# stmsheet.net
KiCad netlist of a schematic drawn in Altium Designer
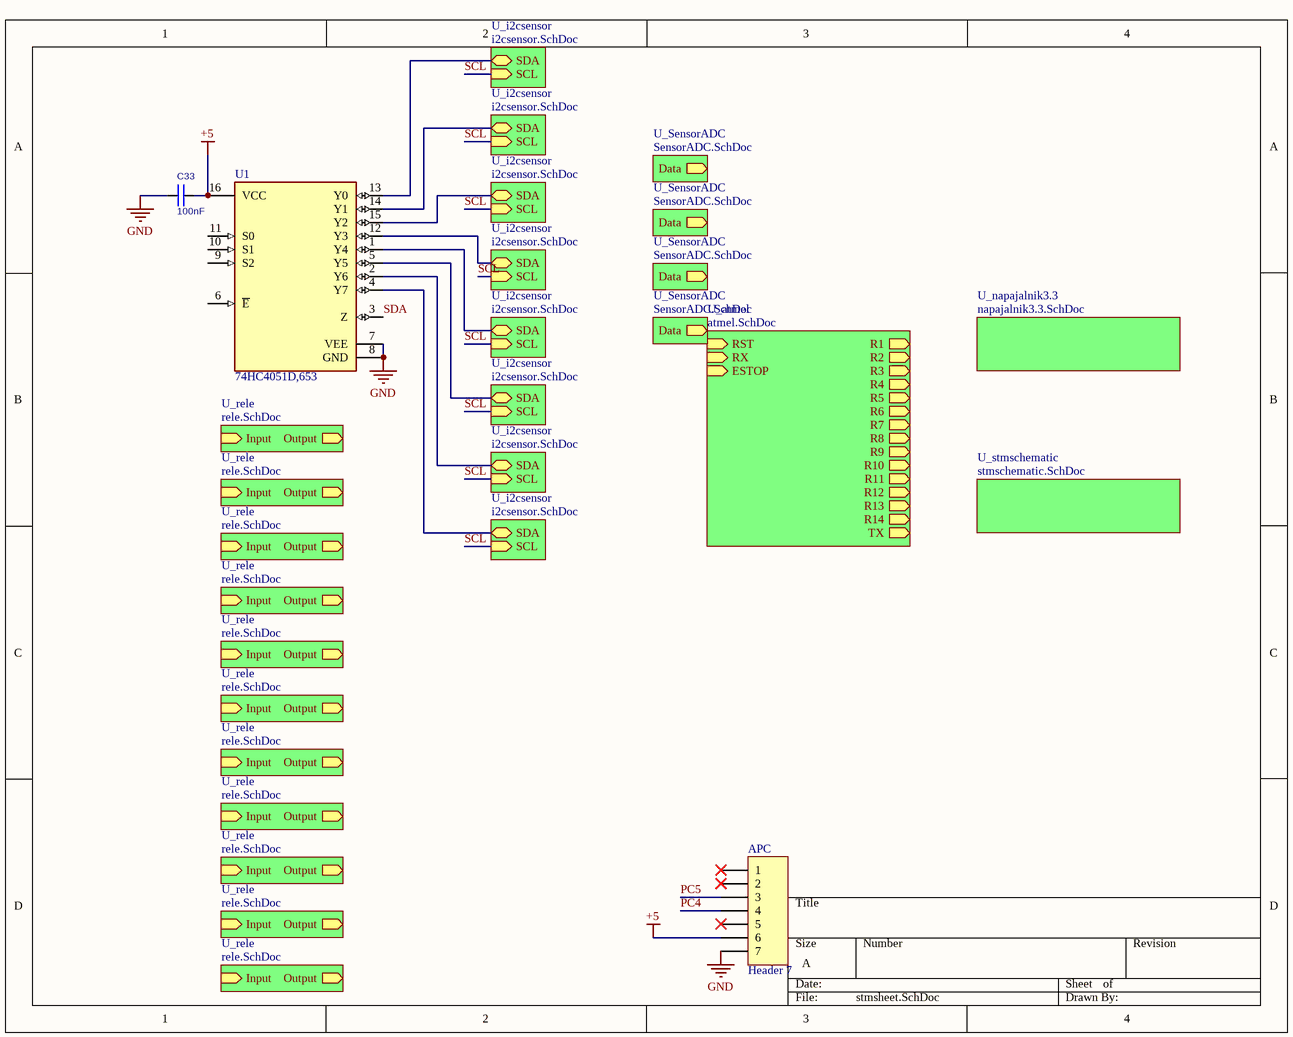
[diagram p0: stmsheet.SchDoc]

(export (version "E")
  (design (tool "Eeschema 10.0.6"))
  (components
    (comp (ref "APC")
      (value "Header 7")
      (footprint "HDR1X7")
      (description "Header, 7-Pin")
      (fields (field (name "PUBLISHER") "Altium Limited"))
      (libsource (lib "Miscellaneous Connectors") (part "Header 7"))
    )
    (comp (ref "C33")
      (value "100nF")
      (footprint "C0603")
      (description "Capacitor")
      (libsource (lib "General") (part "C"))
    )
    (comp (ref "U1")
      (value "74HC4051D,653")
      (footprint "FP-SOT109-1-IPC_B")
      (description "IC MUX/DEMUX 8X1 16SOIC")
      (libsource (lib "Altium Content Vault") (part "f31b6768d3fbbc6ea5534cf41030f6a"))
    )
  )
  (nets
    (net (code "1") (name "+5") (class "Default")
      (node (ref "APC") (pin "6") (pinfunction "6_6") (pintype "passive"))
      (node (ref "C33") (pin "2") (pinfunction "2_2") (pintype "passive"))
      (node (ref "U1") (pin "16") (pinfunction "VCC_16") (pintype "power_in"))
    )
    (net (code "29") (name "/PC4") (class "Default")
      (node (ref "APC") (pin "4") (pinfunction "4_4") (pintype "passive"))
    )
    (net (code "30") (name "/PC5") (class "Default")
      (node (ref "APC") (pin "3") (pinfunction "3_3") (pintype "passive"))
    )
    (net (code "48") (name "/SDA") (class "Default")
      (node (ref "U1") (pin "3") (pinfunction "Z_3") (pintype "bidirectional"))
    )
    (net (code "49") (name "/SDA_1") (class "Default")
      (node (ref "U1") (pin "14") (pinfunction "Y1_14") (pintype "bidirectional"))
    )
    (net (code "50") (name "/SDA_2") (class "Default")
      (node (ref "U1") (pin "15") (pinfunction "Y2_15") (pintype "bidirectional"))
    )
    (net (code "51") (name "/SDA_3") (class "Default")
      (node (ref "U1") (pin "12") (pinfunction "Y3_12") (pintype "bidirectional"))
    )
    (net (code "52") (name "/SDA_4") (class "Default")
      (node (ref "U1") (pin "13") (pinfunction "Y0_13") (pintype "bidirectional"))
    )
    (net (code "53") (name "/SDA_5") (class "Default")
      (node (ref "U1") (pin "1") (pinfunction "Y4_1") (pintype "bidirectional"))
    )
    (net (code "54") (name "/SDA_6") (class "Default")
      (node (ref "U1") (pin "2") (pinfunction "Y6_2") (pintype "bidirectional"))
    )
    (net (code "55") (name "/SDA_7") (class "Default")
      (node (ref "U1") (pin "4") (pinfunction "Y7_4") (pintype "bidirectional"))
    )
    (net (code "56") (name "/SDA_8") (class "Default")
      (node (ref "U1") (pin "5") (pinfunction "Y5_5") (pintype "bidirectional"))
    )
    (net (code "58") (name "GND") (class "Default")
      (node (ref "APC") (pin "7") (pinfunction "7_7") (pintype "passive"))
      (node (ref "C33") (pin "1") (pinfunction "1_1") (pintype "passive"))
      (node (ref "U1") (pin "7") (pinfunction "VEE_7") (pintype "power_in"))
      (node (ref "U1") (pin "8") (pinfunction "GND_8") (pintype "power_in"))
    )
    (net (code "59") (name "unconnected-(APC-Pad1)") (class "Default")
      (node (ref "APC") (pin "1") (pinfunction "1_1") (pintype "passive+no_connect"))
    )
    (net (code "60") (name "unconnected-(APC-Pad2)") (class "Default")
      (node (ref "APC") (pin "2") (pinfunction "2_2") (pintype "passive+no_connect"))
    )
    (net (code "61") (name "unconnected-(APC-Pad5)") (class "Default")
      (node (ref "APC") (pin "5") (pinfunction "5_5") (pintype "passive+no_connect"))
    )
    (net (code "62") (name "unconnected-(U1-S0-Pad11)") (class "Default")
      (node (ref "U1") (pin "11") (pinfunction "S0_11") (pintype "input"))
    )
    (net (code "63") (name "unconnected-(U1-S1-Pad10)") (class "Default")
      (node (ref "U1") (pin "10") (pinfunction "S1_10") (pintype "input"))
    )
    (net (code "64") (name "unconnected-(U1-S2-Pad9)") (class "Default")
      (node (ref "U1") (pin "9") (pinfunction "S2_9") (pintype "input"))
    )
    (net (code "65") (name "unconnected-(U1-~{E}-Pad6)") (class "Default")
      (node (ref "U1") (pin "6") (pinfunction "~{E}_6") (pintype "input"))
    )
  )
)
